# STM32.net
KiCad netlist of a schematic drawn in Altium Designer
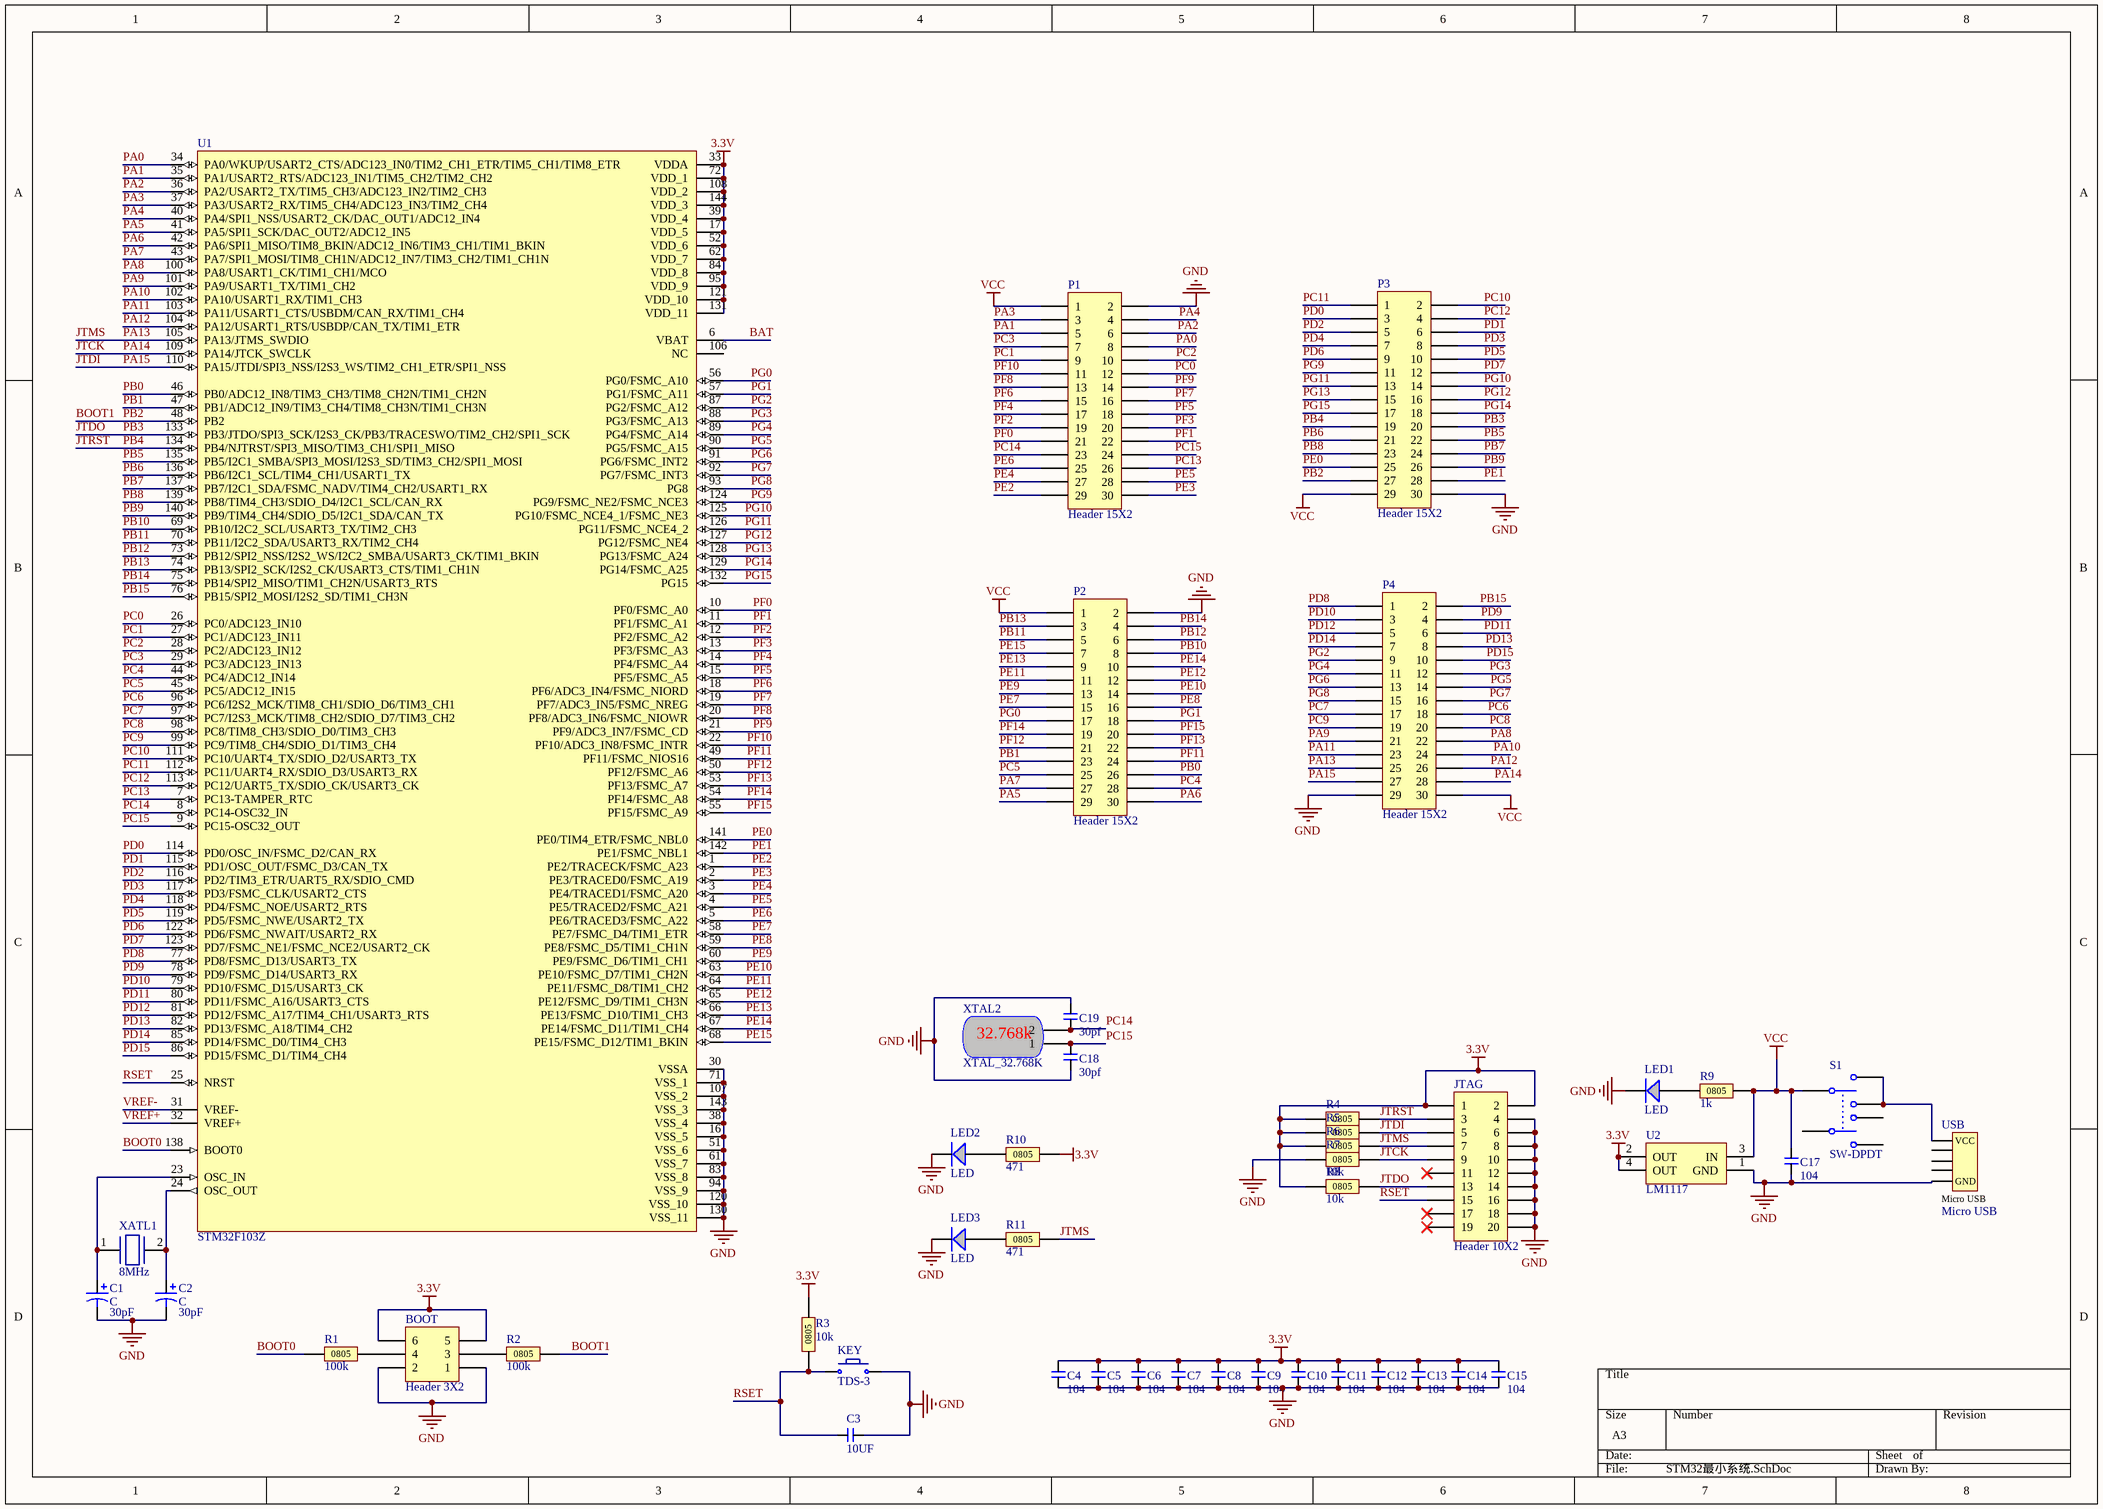
[diagram p0: STM32最小系统.SchDoc]

(export (version "E")
  (design (tool "Eeschema 10.0.6"))
  (components
    (comp (ref "BOOT")
      (value "Header 3X2")
      (footprint "HDR2X3")
      (description "Header, 3-Pin, Dual row")
      (fields (field (name "PUBLISHER") "Altium Limited"))
      (libsource (lib "Miscellaneous Connectors") (part "Header 3X2"))
    )
    (comp (ref "C1")
      (value "C")
      (footprint "C0805")
      (description "Polarized Capacitor (Surface Mount)")
      (fields (field (name "ALTIUM_VALUE") "30pF") (field (name "PUBLISHER") "Altium Limited"))
      (libsource (lib "Miscellaneous Devices") (part "Cap Pol3"))
    )
    (comp (ref "C2")
      (value "C")
      (footprint "C0805")
      (description "Polarized Capacitor (Surface Mount)")
      (fields (field (name "ALTIUM_VALUE") "30pF") (field (name "PUBLISHER") "Altium Limited"))
      (libsource (lib "Miscellaneous Devices") (part "Cap Pol3"))
    )
    (comp (ref "C3") (value "10UF") (footprint "C0805") (libsource (lib "My_Chip") (part "Cap_0805")))
    (comp (ref "C4") (value "104") (footprint "C0805") (libsource (lib "My_Chip") (part "Cap_0805")))
    (comp (ref "C5") (value "104") (footprint "C0805") (libsource (lib "My_Chip") (part "Cap_0805")))
    (comp (ref "C6") (value "104") (footprint "C0805") (libsource (lib "My_Chip") (part "Cap_0805")))
    (comp (ref "C7") (value "104") (footprint "C0805") (libsource (lib "My_Chip") (part "Cap_0805")))
    (comp (ref "C8") (value "104") (footprint "C0805") (libsource (lib "My_Chip") (part "Cap_0805")))
    (comp (ref "C9") (value "104") (footprint "C0805") (libsource (lib "My_Chip") (part "Cap_0805")))
    (comp (ref "C10") (value "104") (footprint "C0805") (libsource (lib "My_Chip") (part "Cap_0805")))
    (comp (ref "C11") (value "104") (footprint "C0805") (libsource (lib "My_Chip") (part "Cap_0805")))
    (comp (ref "C12") (value "104") (footprint "C0805") (libsource (lib "My_Chip") (part "Cap_0805")))
    (comp (ref "C13") (value "104") (footprint "C0805") (libsource (lib "My_Chip") (part "Cap_0805")))
    (comp (ref "C14") (value "104") (footprint "C0805") (libsource (lib "My_Chip") (part "Cap_0805")))
    (comp (ref "C15") (value "104") (footprint "C0805") (libsource (lib "My_Chip") (part "Cap_0805")))
    (comp (ref "C17") (value "104") (footprint "C0805") (libsource (lib "My_Chip") (part "Cap_0805")))
    (comp (ref "C18") (value "30pf") (footprint "C0805") (libsource (lib "My_Chip") (part "Cap_0805")))
    (comp (ref "C19") (value "30pf") (footprint "C0805") (libsource (lib "My_Chip") (part "Cap_0805")))
    (comp (ref "JTAG")
      (value "Header 10X2")
      (footprint "JTAG - duplicate1")
      (description "Header, 10-Pin, Dual row")
      (fields (field (name "PUBLISHER") "Altium Limited"))
      (libsource (lib "Miscellaneous Connectors") (part "Header 10X2"))
    )
    (comp (ref "KEY") (value "TDS-3") (footprint "TDS-3") (libsource (lib "My_Chip") (part "TDS-3")))
    (comp (ref "LED1") (value "LED") (footprint "LED") (libsource (lib "My_Chip") (part "LED")))
    (comp (ref "LED2") (value "LED") (footprint "LED") (libsource (lib "My_Chip") (part "LED")))
    (comp (ref "LED3") (value "LED") (footprint "LED") (libsource (lib "My_Chip") (part "LED")))
    (comp (ref "P1")
      (value "Header 15X2")
      (footprint "HDR2X15")
      (description "Header, 15-Pin, Dual row")
      (fields (field (name "PUBLISHER") "Altium Limited"))
      (libsource (lib "Miscellaneous Connectors") (part "Header 15X2"))
    )
    (comp (ref "P2")
      (value "Header 15X2")
      (footprint "HDR2X15")
      (description "Header, 15-Pin, Dual row")
      (fields (field (name "PUBLISHER") "Altium Limited"))
      (libsource (lib "Miscellaneous Connectors") (part "Header 15X2"))
    )
    (comp (ref "P3")
      (value "Header 15X2")
      (footprint "HDR2X15")
      (description "Header, 15-Pin, Dual row")
      (fields (field (name "PUBLISHER") "Altium Limited"))
      (libsource (lib "Miscellaneous Connectors") (part "Header 15X2"))
    )
    (comp (ref "P4")
      (value "Header 15X2")
      (footprint "HDR2X15")
      (description "Header, 15-Pin, Dual row")
      (fields (field (name "PUBLISHER") "Altium Limited"))
      (libsource (lib "Miscellaneous Connectors") (part "Header 15X2"))
    )
    (comp (ref "R1")
      (value "100k")
      (footprint "PCBComponent_1 - duplicate1")
      (libsource (lib "PCB集成库") (part "贴片电阻"))
    )
    (comp (ref "R2")
      (value "100k")
      (footprint "PCBComponent_1 - duplicate1")
      (libsource (lib "PCB集成库") (part "贴片电阻"))
    )
    (comp (ref "R3")
      (value "10k")
      (footprint "PCBComponent_1 - duplicate1")
      (libsource (lib "") (part "贴片电阻_1"))
    )
    (comp (ref "R4")
      (value "10k")
      (footprint "PCBComponent_1 - duplicate1")
      (libsource (lib "PCB集成库") (part "贴片电阻"))
    )
    (comp (ref "R5")
      (value "10k")
      (footprint "PCBComponent_1 - duplicate1")
      (libsource (lib "PCB集成库") (part "贴片电阻"))
    )
    (comp (ref "R6")
      (value "10k")
      (footprint "PCBComponent_1 - duplicate1")
      (libsource (lib "PCB集成库") (part "贴片电阻"))
    )
    (comp (ref "R7")
      (value "10k")
      (footprint "PCBComponent_1 - duplicate1")
      (libsource (lib "PCB集成库") (part "贴片电阻"))
    )
    (comp (ref "R8")
      (value "10k")
      (footprint "PCBComponent_1 - duplicate1")
      (libsource (lib "PCB集成库") (part "贴片电阻"))
    )
    (comp (ref "R9")
      (value "1k")
      (footprint "PCBComponent_1 - duplicate1")
      (libsource (lib "PCB集成库") (part "贴片电阻"))
    )
    (comp (ref "R10")
      (value "471")
      (footprint "PCBComponent_1 - duplicate1")
      (libsource (lib "PCB集成库") (part "贴片电阻"))
    )
    (comp (ref "R11")
      (value "471")
      (footprint "PCBComponent_1 - duplicate1")
      (libsource (lib "PCB集成库") (part "贴片电阻"))
    )
    (comp (ref "S1")
      (value "SW-DPDT")
      (footprint "DPDT-6")
      (description "Double-Pole, Double-Throw Switch")
      (fields (field (name "PUBLISHER") "Altium Limited"))
      (libsource (lib "Miscellaneous Devices") (part "SW-DPDT"))
    )
    (comp (ref "U1")
      (value "STM32F103Z")
      (footprint "LQFP-144N")
      (libsource (lib "stm32") (part "STM32F103Z_T"))
    )
    (comp (ref "U2") (value "LM1117") (footprint "SOT-223") (libsource (lib "My_Chip") (part "LM1117")))
    (comp (ref "USB")
      (value "Micro USB")
      (footprint "PCBComponent_1 - duplicate2")
      (libsource (lib "PCB集成库") (part "Micro USB"))
    )
    (comp (ref "XATL1") (value "8MHz") (footprint "49/S_N") (libsource (lib "My_Chip") (part "XATL")))
    (comp (ref "XTAL2")
      (value "XTAL_32.768K")
      (footprint "XTAL_32.768K")
      (libsource (lib "My_Chip") (part "XTAL_32.768K"))
    )
  )
  (nets
    (net (code "1") (name "/BAT") (class "Default")
      (node (ref "U1") (pin "6") (pinfunction "VBAT_6") (pintype "power_in"))
    )
    (net (code "2") (name "/BOOT0") (class "Default")
      (node (ref "R1") (pin "1") (pinfunction "10_1") (pintype "passive"))
      (node (ref "U1") (pin "138") (pinfunction "BOOT0_138") (pintype "input"))
    )
    (net (code "3") (name "/BOOT1") (class "Default")
      (node (ref "P3") (pin "27") (pinfunction "27_27") (pintype "passive"))
      (node (ref "R2") (pin "2") (pinfunction "11_2") (pintype "passive"))
      (node (ref "U1") (pin "48") (pinfunction "PB2_48") (pintype "bidirectional"))
    )
    (net (code "4") (name "/JTCK") (class "Default")
      (node (ref "JTAG") (pin "9") (pinfunction "9_9") (pintype "passive"))
      (node (ref "P4") (pin "28") (pinfunction "28_28") (pintype "passive"))
      (node (ref "R7") (pin "2") (pinfunction "11_2") (pintype "passive"))
      (node (ref "U1") (pin "109") (pinfunction "PA14/JTCK_SWCLK_109") (pintype "bidirectional"))
    )
    (net (code "5") (name "/JTDI") (class "Default")
      (node (ref "JTAG") (pin "5") (pinfunction "5_5") (pintype "passive"))
      (node (ref "P4") (pin "27") (pinfunction "27_27") (pintype "passive"))
      (node (ref "R5") (pin "2") (pinfunction "11_2") (pintype "passive"))
      (node (ref "U1") (pin "110") (pinfunction "PA15/JTDI/SPI3_NSS/I2S3_WS/TIM2_CH1_ETR/SPI1_NSS_110") (pintype "bidirectional"))
    )
    (net (code "6") (name "/JTDO") (class "Default")
      (node (ref "JTAG") (pin "13") (pinfunction "13_13") (pintype "passive"))
      (node (ref "P3") (pin "20") (pinfunction "20_20") (pintype "passive"))
      (node (ref "R8") (pin "2") (pinfunction "11_2") (pintype "passive"))
      (node (ref "U1") (pin "133") (pinfunction "PB3/JTDO/SPI3_SCK/I2S3_CK/PB3/TRACESWO/TIM2_CH2/SPI1_SCK_133") (pintype "bidirectional"))
    )
    (net (code "7") (name "/JTMS") (class "Default")
      (node (ref "JTAG") (pin "7") (pinfunction "7_7") (pintype "passive"))
      (node (ref "P4") (pin "25") (pinfunction "25_25") (pintype "passive"))
      (node (ref "R11") (pin "2") (pinfunction "11_2") (pintype "passive"))
      (node (ref "R6") (pin "2") (pinfunction "11_2") (pintype "passive"))
      (node (ref "U1") (pin "105") (pinfunction "PA13/JTMS_SWDIO_105") (pintype "bidirectional"))
    )
    (net (code "8") (name "/JTRST") (class "Default")
      (node (ref "JTAG") (pin "3") (pinfunction "3_3") (pintype "passive"))
      (node (ref "P3") (pin "19") (pinfunction "19_19") (pintype "passive"))
      (node (ref "R4") (pin "2") (pinfunction "11_2") (pintype "passive"))
      (node (ref "U1") (pin "134") (pinfunction "PB4/NJTRST/SPI3_MISO/TIM3_CH1/SPI1_MISO_134") (pintype "bidirectional"))
    )
    (net (code "9") (name "/PA0") (class "Default")
      (node (ref "P1") (pin "8") (pinfunction "8_8") (pintype "passive"))
      (node (ref "U1") (pin "34") (pinfunction "PA0/WKUP/USART2_CTS/ADC123_IN0/TIM2_CH1_ETR/TIM5_CH1/TIM8_ETR_34") (pintype "bidirectional"))
    )
    (net (code "10") (name "/PA1") (class "Default")
      (node (ref "P1") (pin "5") (pinfunction "5_5") (pintype "passive"))
      (node (ref "U1") (pin "35") (pinfunction "PA1/USART2_RTS/ADC123_IN1/TIM5_CH2/TIM2_CH2_35") (pintype "bidirectional"))
    )
    (net (code "11") (name "/PA2") (class "Default")
      (node (ref "P1") (pin "6") (pinfunction "6_6") (pintype "passive"))
      (node (ref "U1") (pin "36") (pinfunction "PA2/USART2_TX/TIM5_CH3/ADC123_IN2/TIM2_CH3_36") (pintype "bidirectional"))
    )
    (net (code "12") (name "/PA3") (class "Default")
      (node (ref "P1") (pin "3") (pinfunction "3_3") (pintype "passive"))
      (node (ref "U1") (pin "37") (pinfunction "PA3/USART2_RX/TIM5_CH4/ADC123_IN3/TIM2_CH4_37") (pintype "bidirectional"))
    )
    (net (code "13") (name "/PA4") (class "Default")
      (node (ref "P1") (pin "4") (pinfunction "4_4") (pintype "passive"))
      (node (ref "U1") (pin "40") (pinfunction "PA4/SPI1_NSS/USART2_CK/DAC_OUT1/ADC12_IN4_40") (pintype "bidirectional"))
    )
    (net (code "14") (name "/PA5") (class "Default")
      (node (ref "P2") (pin "29") (pinfunction "29_29") (pintype "passive"))
      (node (ref "U1") (pin "41") (pinfunction "PA5/SPI1_SCK/DAC_OUT2/ADC12_IN5_41") (pintype "bidirectional"))
    )
    (net (code "15") (name "/PA6") (class "Default")
      (node (ref "P2") (pin "30") (pinfunction "30_30") (pintype "passive"))
      (node (ref "U1") (pin "42") (pinfunction "PA6/SPI1_MISO/TIM8_BKIN/ADC12_IN6/TIM3_CH1/TIM1_BKIN_42") (pintype "bidirectional"))
    )
    (net (code "16") (name "/PA7") (class "Default")
      (node (ref "P2") (pin "27") (pinfunction "27_27") (pintype "passive"))
      (node (ref "U1") (pin "43") (pinfunction "PA7/SPI1_MOSI/TIM8_CH1N/ADC12_IN7/TIM3_CH2/TIM1_CH1N_43") (pintype "bidirectional"))
    )
    (net (code "17") (name "/PA8") (class "Default")
      (node (ref "P4") (pin "22") (pinfunction "22_22") (pintype "passive"))
      (node (ref "U1") (pin "100") (pinfunction "PA8/USART1_CK/TIM1_CH1/MCO_100") (pintype "bidirectional"))
    )
    (net (code "18") (name "/PA9") (class "Default")
      (node (ref "P4") (pin "21") (pinfunction "21_21") (pintype "passive"))
      (node (ref "U1") (pin "101") (pinfunction "PA9/USART1_TX/TIM1_CH2_101") (pintype "bidirectional"))
    )
    (net (code "19") (name "/PA10") (class "Default")
      (node (ref "P4") (pin "24") (pinfunction "24_24") (pintype "passive"))
      (node (ref "U1") (pin "102") (pinfunction "PA10/USART1_RX/TIM1_CH3_102") (pintype "bidirectional"))
    )
    (net (code "20") (name "/PA11") (class "Default")
      (node (ref "P4") (pin "23") (pinfunction "23_23") (pintype "passive"))
      (node (ref "U1") (pin "103") (pinfunction "PA11/USART1_CTS/USBDM/CAN_RX/TIM1_CH4_103") (pintype "bidirectional"))
    )
    (net (code "21") (name "/PA12") (class "Default")
      (node (ref "P4") (pin "26") (pinfunction "26_26") (pintype "passive"))
      (node (ref "U1") (pin "104") (pinfunction "PA12/USART1_RTS/USBDP/CAN_TX/TIM1_ETR_104") (pintype "bidirectional"))
    )
    (net (code "22") (name "/PB0") (class "Default")
      (node (ref "P2") (pin "26") (pinfunction "26_26") (pintype "passive"))
      (node (ref "U1") (pin "46") (pinfunction "PB0/ADC12_IN8/TIM3_CH3/TIM8_CH2N/TIM1_CH2N_46") (pintype "bidirectional"))
    )
    (net (code "23") (name "/PB1") (class "Default")
      (node (ref "P2") (pin "23") (pinfunction "23_23") (pintype "passive"))
      (node (ref "U1") (pin "47") (pinfunction "PB1/ADC12_IN9/TIM3_CH4/TIM8_CH3N/TIM1_CH3N_47") (pintype "bidirectional"))
    )
    (net (code "24") (name "/PB5") (class "Default")
      (node (ref "P3") (pin "22") (pinfunction "22_22") (pintype "passive"))
      (node (ref "U1") (pin "135") (pinfunction "PB5/I2C1_SMBA/SPI3_MOSI/I2S3_SD/TIM3_CH2/SPI1_MOSI_135") (pintype "bidirectional"))
    )
    (net (code "25") (name "/PB6") (class "Default")
      (node (ref "P3") (pin "21") (pinfunction "21_21") (pintype "passive"))
      (node (ref "U1") (pin "136") (pinfunction "PB6/I2C1_SCL/TIM4_CH1/USART1_TX_136") (pintype "bidirectional"))
    )
    (net (code "26") (name "/PB7") (class "Default")
      (node (ref "P3") (pin "24") (pinfunction "24_24") (pintype "passive"))
      (node (ref "U1") (pin "137") (pinfunction "PB7/I2C1_SDA/FSMC_NADV/TIM4_CH2/USART1_RX_137") (pintype "bidirectional"))
    )
    (net (code "27") (name "/PB8") (class "Default")
      (node (ref "P3") (pin "23") (pinfunction "23_23") (pintype "passive"))
      (node (ref "U1") (pin "139") (pinfunction "PB8/TIM4_CH3/SDIO_D4/I2C1_SCL/CAN_RX_139") (pintype "bidirectional"))
    )
    (net (code "28") (name "/PB9") (class "Default")
      (node (ref "P3") (pin "26") (pinfunction "26_26") (pintype "passive"))
      (node (ref "U1") (pin "140") (pinfunction "PB9/TIM4_CH4/SDIO_D5/I2C1_SDA/CAN_TX_140") (pintype "bidirectional"))
    )
    (net (code "29") (name "/PB10") (class "Default")
      (node (ref "P2") (pin "8") (pinfunction "8_8") (pintype "passive"))
      (node (ref "U1") (pin "69") (pinfunction "PB10/I2C2_SCL/USART3_TX/TIM2_CH3_69") (pintype "bidirectional"))
    )
    (net (code "30") (name "/PB11") (class "Default")
      (node (ref "P2") (pin "5") (pinfunction "5_5") (pintype "passive"))
      (node (ref "U1") (pin "70") (pinfunction "PB11/I2C2_SDA/USART3_RX/TIM2_CH4_70") (pintype "bidirectional"))
    )
    (net (code "31") (name "/PB12") (class "Default")
      (node (ref "P2") (pin "6") (pinfunction "6_6") (pintype "passive"))
      (node (ref "U1") (pin "73") (pinfunction "PB12/SPI2_NSS/I2S2_WS/I2C2_SMBA/USART3_CK/TIM1_BKIN_73") (pintype "bidirectional"))
    )
    (net (code "32") (name "/PB13") (class "Default")
      (node (ref "P2") (pin "3") (pinfunction "3_3") (pintype "passive"))
      (node (ref "U1") (pin "74") (pinfunction "PB13/SPI2_SCK/I2S2_CK/USART3_CTS/TIM1_CH1N_74") (pintype "bidirectional"))
    )
    (net (code "33") (name "/PB14") (class "Default")
      (node (ref "P2") (pin "4") (pinfunction "4_4") (pintype "passive"))
      (node (ref "U1") (pin "75") (pinfunction "PB14/SPI2_MISO/TIM1_CH2N/USART3_RTS_75") (pintype "bidirectional"))
    )
    (net (code "34") (name "/PB15") (class "Default")
      (node (ref "P4") (pin "2") (pinfunction "2_2") (pintype "passive"))
      (node (ref "U1") (pin "76") (pinfunction "PB15/SPI2_MOSI/I2S2_SD/TIM1_CH3N_76") (pintype "bidirectional"))
    )
    (net (code "35") (name "/PC0") (class "Default")
      (node (ref "P1") (pin "12") (pinfunction "12_12") (pintype "passive"))
      (node (ref "U1") (pin "26") (pinfunction "PC0/ADC123_IN10_26") (pintype "bidirectional"))
    )
    (net (code "36") (name "/PC1") (class "Default")
      (node (ref "P1") (pin "9") (pinfunction "9_9") (pintype "passive"))
      (node (ref "U1") (pin "27") (pinfunction "PC1/ADC123_IN11_27") (pintype "bidirectional"))
    )
    (net (code "37") (name "/PC2") (class "Default")
      (node (ref "P1") (pin "10") (pinfunction "10_10") (pintype "passive"))
      (node (ref "U1") (pin "28") (pinfunction "PC2/ADC123_IN12_28") (pintype "bidirectional"))
    )
    (net (code "38") (name "/PC3") (class "Default")
      (node (ref "P1") (pin "7") (pinfunction "7_7") (pintype "passive"))
      (node (ref "U1") (pin "29") (pinfunction "PC3/ADC123_IN13_29") (pintype "bidirectional"))
    )
    (net (code "39") (name "/PC4") (class "Default")
      (node (ref "P2") (pin "28") (pinfunction "28_28") (pintype "passive"))
      (node (ref "U1") (pin "44") (pinfunction "PC4/ADC12_IN14_44") (pintype "bidirectional"))
    )
    (net (code "40") (name "/PC5") (class "Default")
      (node (ref "P2") (pin "25") (pinfunction "25_25") (pintype "passive"))
      (node (ref "U1") (pin "45") (pinfunction "PC5/ADC12_IN15_45") (pintype "bidirectional"))
    )
    (net (code "41") (name "/PC6") (class "Default")
      (node (ref "P4") (pin "18") (pinfunction "18_18") (pintype "passive"))
      (node (ref "U1") (pin "96") (pinfunction "PC6/I2S2_MCK/TIM8_CH1/SDIO_D6/TIM3_CH1_96") (pintype "bidirectional"))
    )
    (net (code "42") (name "/PC7") (class "Default")
      (node (ref "P4") (pin "17") (pinfunction "17_17") (pintype "passive"))
      (node (ref "U1") (pin "97") (pinfunction "PC7/I2S3_MCK/TIM8_CH2/SDIO_D7/TIM3_CH2_97") (pintype "bidirectional"))
    )
    (net (code "43") (name "/PC8") (class "Default")
      (node (ref "P4") (pin "20") (pinfunction "20_20") (pintype "passive"))
      (node (ref "U1") (pin "98") (pinfunction "PC8/TIM8_CH3/SDIO_D0/TIM3_CH3_98") (pintype "bidirectional"))
    )
    (net (code "44") (name "/PC9") (class "Default")
      (node (ref "P4") (pin "19") (pinfunction "19_19") (pintype "passive"))
      (node (ref "U1") (pin "99") (pinfunction "PC9/TIM8_CH4/SDIO_D1/TIM3_CH4_99") (pintype "bidirectional"))
    )
    (net (code "45") (name "/PC10") (class "Default")
      (node (ref "P3") (pin "2") (pinfunction "2_2") (pintype "passive"))
      (node (ref "U1") (pin "111") (pinfunction "PC10/UART4_TX/SDIO_D2/USART3_TX_111") (pintype "bidirectional"))
    )
    (net (code "46") (name "/PC11") (class "Default")
      (node (ref "P3") (pin "1") (pinfunction "1_1") (pintype "passive"))
      (node (ref "U1") (pin "112") (pinfunction "PC11/UART4_RX/SDIO_D3/USART3_RX_112") (pintype "bidirectional"))
    )
    (net (code "47") (name "/PC12") (class "Default")
      (node (ref "P3") (pin "4") (pinfunction "4_4") (pintype "passive"))
      (node (ref "U1") (pin "113") (pinfunction "PC12/UART5_TX/SDIO_CK/USART3_CK_113") (pintype "bidirectional"))
    )
    (net (code "48") (name "/PC13") (class "Default")
      (node (ref "P1") (pin "26") (pinfunction "26_26") (pintype "passive"))
      (node (ref "U1") (pin "7") (pinfunction "PC13-TAMPER_RTC_7") (pintype "bidirectional"))
    )
    (net (code "49") (name "/PC14") (class "Default")
      (node (ref "C19") (pin "1") (pinfunction "1_1") (pintype "passive"))
      (node (ref "P1") (pin "23") (pinfunction "23_23") (pintype "passive"))
      (node (ref "U1") (pin "8") (pinfunction "PC14-OSC32_IN_8") (pintype "bidirectional"))
      (node (ref "XTAL2") (pin "2") (pinfunction "2_2") (pintype "passive"))
    )
    (net (code "50") (name "/PC15") (class "Default")
      (node (ref "C18") (pin "2") (pinfunction "2_2") (pintype "passive"))
      (node (ref "P1") (pin "24") (pinfunction "24_24") (pintype "passive"))
      (node (ref "U1") (pin "9") (pinfunction "PC15-OSC32_OUT_9") (pintype "bidirectional"))
      (node (ref "XTAL2") (pin "1") (pinfunction "1_1") (pintype "passive"))
    )
    (net (code "51") (name "/PD0") (class "Default")
      (node (ref "P3") (pin "3") (pinfunction "3_3") (pintype "passive"))
      (node (ref "U1") (pin "114") (pinfunction "PD0/OSC_IN/FSMC_D2/CAN_RX_114") (pintype "bidirectional"))
    )
    (net (code "52") (name "/PD1") (class "Default")
      (node (ref "P3") (pin "6") (pinfunction "6_6") (pintype "passive"))
      (node (ref "U1") (pin "115") (pinfunction "PD1/OSC_OUT/FSMC_D3/CAN_TX_115") (pintype "bidirectional"))
    )
    (net (code "53") (name "/PD2") (class "Default")
      (node (ref "P3") (pin "5") (pinfunction "5_5") (pintype "passive"))
      (node (ref "U1") (pin "116") (pinfunction "PD2/TIM3_ETR/UART5_RX/SDIO_CMD_116") (pintype "bidirectional"))
    )
    (net (code "54") (name "/PD3") (class "Default")
      (node (ref "P3") (pin "8") (pinfunction "8_8") (pintype "passive"))
      (node (ref "U1") (pin "117") (pinfunction "PD3/FSMC_CLK/USART2_CTS_117") (pintype "bidirectional"))
    )
    (net (code "55") (name "/PD4") (class "Default")
      (node (ref "P3") (pin "7") (pinfunction "7_7") (pintype "passive"))
      (node (ref "U1") (pin "118") (pinfunction "PD4/FSMC_NOE/USART2_RTS_118") (pintype "bidirectional"))
    )
    (net (code "56") (name "/PD5") (class "Default")
      (node (ref "P3") (pin "10") (pinfunction "10_10") (pintype "passive"))
      (node (ref "U1") (pin "119") (pinfunction "PD5/FSMC_NWE/USART2_TX_119") (pintype "bidirectional"))
    )
    (net (code "57") (name "/PD6") (class "Default")
      (node (ref "P3") (pin "9") (pinfunction "9_9") (pintype "passive"))
      (node (ref "U1") (pin "122") (pinfunction "PD6/FSMC_NWAIT/USART2_RX_122") (pintype "bidirectional"))
    )
    (net (code "58") (name "/PD7") (class "Default")
      (node (ref "P3") (pin "12") (pinfunction "12_12") (pintype "passive"))
      (node (ref "U1") (pin "123") (pinfunction "PD7/FSMC_NE1/FSMC_NCE2/USART2_CK_123") (pintype "bidirectional"))
    )
    (net (code "59") (name "/PD8") (class "Default")
      (node (ref "P4") (pin "1") (pinfunction "1_1") (pintype "passive"))
      (node (ref "U1") (pin "77") (pinfunction "PD8/FSMC_D13/USART3_TX_77") (pintype "bidirectional"))
    )
    (net (code "60") (name "/PD9") (class "Default")
      (node (ref "P4") (pin "4") (pinfunction "4_4") (pintype "passive"))
      (node (ref "U1") (pin "78") (pinfunction "PD9/FSMC_D14/USART3_RX_78") (pintype "bidirectional"))
    )
    (net (code "61") (name "/PD10") (class "Default")
      (node (ref "P4") (pin "3") (pinfunction "3_3") (pintype "passive"))
      (node (ref "U1") (pin "79") (pinfunction "PD10/FSMC_D15/USART3_CK_79") (pintype "bidirectional"))
    )
    (net (code "62") (name "/PD11") (class "Default")
      (node (ref "P4") (pin "6") (pinfunction "6_6") (pintype "passive"))
      (node (ref "U1") (pin "80") (pinfunction "PD11/FSMC_A16/USART3_CTS_80") (pintype "bidirectional"))
    )
    (net (code "63") (name "/PD12") (class "Default")
      (node (ref "P4") (pin "5") (pinfunction "5_5") (pintype "passive"))
      (node (ref "U1") (pin "81") (pinfunction "PD12/FSMC_A17/TIM4_CH1/USART3_RTS_81") (pintype "bidirectional"))
    )
    (net (code "64") (name "/PD13") (class "Default")
      (node (ref "P4") (pin "8") (pinfunction "8_8") (pintype "passive"))
      (node (ref "U1") (pin "82") (pinfunction "PD13/FSMC_A18/TIM4_CH2_82") (pintype "bidirectional"))
    )
    (net (code "65") (name "/PD14") (class "Default")
      (node (ref "P4") (pin "7") (pinfunction "7_7") (pintype "passive"))
      (node (ref "U1") (pin "85") (pinfunction "PD14/FSMC_D0/TIM4_CH3_85") (pintype "bidirectional"))
    )
    (net (code "66") (name "/PD15") (class "Default")
      (node (ref "P4") (pin "10") (pinfunction "10_10") (pintype "passive"))
      (node (ref "U1") (pin "86") (pinfunction "PD15/FSMC_D1/TIM4_CH4_86") (pintype "bidirectional"))
    )
    (net (code "67") (name "/PE0") (class "Default")
      (node (ref "P3") (pin "25") (pinfunction "25_25") (pintype "passive"))
      (node (ref "U1") (pin "141") (pinfunction "PE0/TIM4_ETR/FSMC_NBL0_141") (pintype "bidirectional"))
    )
    (net (code "68") (name "/PE1") (class "Default")
      (node (ref "P3") (pin "28") (pinfunction "28_28") (pintype "passive"))
      (node (ref "U1") (pin "142") (pinfunction "PE1/FSMC_NBL1_142") (pintype "bidirectional"))
    )
    (net (code "69") (name "/PE2") (class "Default")
      (node (ref "P1") (pin "29") (pinfunction "29_29") (pintype "passive"))
      (node (ref "U1") (pin "1") (pinfunction "PE2/TRACECK/FSMC_A23_1") (pintype "bidirectional"))
    )
    (net (code "70") (name "/PE3") (class "Default")
      (node (ref "P1") (pin "30") (pinfunction "30_30") (pintype "passive"))
      (node (ref "U1") (pin "2") (pinfunction "PE3/TRACED0/FSMC_A19_2") (pintype "bidirectional"))
    )
    (net (code "71") (name "/PE4") (class "Default")
      (node (ref "P1") (pin "27") (pinfunction "27_27") (pintype "passive"))
      (node (ref "U1") (pin "3") (pinfunction "PE4/TRACED1/FSMC_A20_3") (pintype "bidirectional"))
    )
    (net (code "72") (name "/PE5") (class "Default")
      (node (ref "P1") (pin "28") (pinfunction "28_28") (pintype "passive"))
      (node (ref "U1") (pin "4") (pinfunction "PE5/TRACED2/FSMC_A21_4") (pintype "bidirectional"))
    )
    (net (code "73") (name "/PE6") (class "Default")
      (node (ref "P1") (pin "25") (pinfunction "25_25") (pintype "passive"))
      (node (ref "U1") (pin "5") (pinfunction "PE6/TRACED3/FSMC_A22_5") (pintype "bidirectional"))
    )
    (net (code "74") (name "/PE7") (class "Default")
      (node (ref "P2") (pin "15") (pinfunction "15_15") (pintype "passive"))
      (node (ref "U1") (pin "58") (pinfunction "PE7/FSMC_D4/TIM1_ETR_58") (pintype "bidirectional"))
    )
    (net (code "75") (name "/PE8") (class "Default")
      (node (ref "P2") (pin "16") (pinfunction "16_16") (pintype "passive"))
      (node (ref "U1") (pin "59") (pinfunction "PE8/FSMC_D5/TIM1_CH1N_59") (pintype "bidirectional"))
    )
    (net (code "76") (name "/PE9") (class "Default")
      (node (ref "P2") (pin "13") (pinfunction "13_13") (pintype "passive"))
      (node (ref "U1") (pin "60") (pinfunction "PE9/FSMC_D6/TIM1_CH1_60") (pintype "bidirectional"))
    )
    (net (code "77") (name "/PE10") (class "Default")
      (node (ref "P2") (pin "14") (pinfunction "14_14") (pintype "passive"))
      (node (ref "U1") (pin "63") (pinfunction "PE10/FSMC_D7/TIM1_CH2N_63") (pintype "bidirectional"))
    )
    (net (code "78") (name "/PE11") (class "Default")
      (node (ref "P2") (pin "11") (pinfunction "11_11") (pintype "passive"))
      (node (ref "U1") (pin "64") (pinfunction "PE11/FSMC_D8/TIM1_CH2_64") (pintype "bidirectional"))
    )
    (net (code "79") (name "/PE12") (class "Default")
      (node (ref "P2") (pin "12") (pinfunction "12_12") (pintype "passive"))
      (node (ref "U1") (pin "65") (pinfunction "PE12/FSMC_D9/TIM1_CH3N_65") (pintype "bidirectional"))
    )
    (net (code "80") (name "/PE13") (class "Default")
      (node (ref "P2") (pin "9") (pinfunction "9_9") (pintype "passive"))
      (node (ref "U1") (pin "66") (pinfunction "PE13/FSMC_D10/TIM1_CH3_66") (pintype "bidirectional"))
    )
    (net (code "81") (name "/PE14") (class "Default")
      (node (ref "P2") (pin "10") (pinfunction "10_10") (pintype "passive"))
      (node (ref "U1") (pin "67") (pinfunction "PE14/FSMC_D11/TIM1_CH4_67") (pintype "bidirectional"))
    )
    (net (code "82") (name "/PE15") (class "Default")
      (node (ref "P2") (pin "7") (pinfunction "7_7") (pintype "passive"))
      (node (ref "U1") (pin "68") (pinfunction "PE15/FSMC_D12/TIM1_BKIN_68") (pintype "bidirectional"))
    )
    (net (code "83") (name "/PF0") (class "Default")
      (node (ref "P1") (pin "21") (pinfunction "21_21") (pintype "passive"))
      (node (ref "U1") (pin "10") (pinfunction "PF0/FSMC_A0_10") (pintype "bidirectional"))
    )
    (net (code "84") (name "/PF1") (class "Default")
      (node (ref "P1") (pin "22") (pinfunction "22_22") (pintype "passive"))
      (node (ref "U1") (pin "11") (pinfunction "PF1/FSMC_A1_11") (pintype "bidirectional"))
    )
    (net (code "85") (name "/PF2") (class "Default")
      (node (ref "P1") (pin "19") (pinfunction "19_19") (pintype "passive"))
      (node (ref "U1") (pin "12") (pinfunction "PF2/FSMC_A2_12") (pintype "bidirectional"))
    )
    (net (code "86") (name "/PF3") (class "Default")
      (node (ref "P1") (pin "20") (pinfunction "20_20") (pintype "passive"))
      (node (ref "U1") (pin "13") (pinfunction "PF3/FSMC_A3_13") (pintype "bidirectional"))
    )
    (net (code "87") (name "/PF4") (class "Default")
      (node (ref "P1") (pin "17") (pinfunction "17_17") (pintype "passive"))
      (node (ref "U1") (pin "14") (pinfunction "PF4/FSMC_A4_14") (pintype "bidirectional"))
    )
    (net (code "88") (name "/PF5") (class "Default")
      (node (ref "P1") (pin "18") (pinfunction "18_18") (pintype "passive"))
      (node (ref "U1") (pin "15") (pinfunction "PF5/FSMC_A5_15") (pintype "bidirectional"))
    )
    (net (code "89") (name "/PF6") (class "Default")
      (node (ref "P1") (pin "15") (pinfunction "15_15") (pintype "passive"))
      (node (ref "U1") (pin "18") (pinfunction "PF6/ADC3_IN4/FSMC_NIORD_18") (pintype "bidirectional"))
    )
    (net (code "90") (name "/PF7") (class "Default")
      (node (ref "P1") (pin "16") (pinfunction "16_16") (pintype "passive"))
      (node (ref "U1") (pin "19") (pinfunction "PF7/ADC3_IN5/FSMC_NREG_19") (pintype "bidirectional"))
    )
    (net (code "91") (name "/PF8") (class "Default")
      (node (ref "P1") (pin "13") (pinfunction "13_13") (pintype "passive"))
      (node (ref "U1") (pin "20") (pinfunction "PF8/ADC3_IN6/FSMC_NIOWR_20") (pintype "bidirectional"))
    )
    (net (code "92") (name "/PF9") (class "Default")
      (node (ref "P1") (pin "14") (pinfunction "14_14") (pintype "passive"))
      (node (ref "U1") (pin "21") (pinfunction "PF9/ADC3_IN7/FSMC_CD_21") (pintype "bidirectional"))
    )
    (net (code "93") (name "/PF10") (class "Default")
      (node (ref "P1") (pin "11") (pinfunction "11_11") (pintype "passive"))
      (node (ref "U1") (pin "22") (pinfunction "PF10/ADC3_IN8/FSMC_INTR_22") (pintype "bidirectional"))
    )
    (net (code "94") (name "/PF11") (class "Default")
      (node (ref "P2") (pin "24") (pinfunction "24_24") (pintype "passive"))
      (node (ref "U1") (pin "49") (pinfunction "PF11/FSMC_NIOS16_49") (pintype "bidirectional"))
    )
    (net (code "95") (name "/PF12") (class "Default")
      (node (ref "P2") (pin "21") (pinfunction "21_21") (pintype "passive"))
      (node (ref "U1") (pin "50") (pinfunction "PF12/FSMC_A6_50") (pintype "bidirectional"))
    )
    (net (code "96") (name "/PF13") (class "Default")
      (node (ref "P2") (pin "22") (pinfunction "22_22") (pintype "passive"))
      (node (ref "U1") (pin "53") (pinfunction "PF13/FSMC_A7_53") (pintype "bidirectional"))
    )
    (net (code "97") (name "/PF14") (class "Default")
      (node (ref "P2") (pin "19") (pinfunction "19_19") (pintype "passive"))
      (node (ref "U1") (pin "54") (pinfunction "PF14/FSMC_A8_54") (pintype "bidirectional"))
    )
    (net (code "98") (name "/PF15") (class "Default")
      (node (ref "P2") (pin "20") (pinfunction "20_20") (pintype "passive"))
      (node (ref "U1") (pin "55") (pinfunction "PF15/FSMC_A9_55") (pintype "bidirectional"))
    )
    (net (code "99") (name "/PG0") (class "Default")
      (node (ref "P2") (pin "17") (pinfunction "17_17") (pintype "passive"))
      (node (ref "U1") (pin "56") (pinfunction "PG0/FSMC_A10_56") (pintype "bidirectional"))
    )
    (net (code "100") (name "/PG1") (class "Default")
      (node (ref "P2") (pin "18") (pinfunction "18_18") (pintype "passive"))
      (node (ref "U1") (pin "57") (pinfunction "PG1/FSMC_A11_57") (pintype "bidirectional"))
    )
    (net (code "101") (name "/PG2") (class "Default")
      (node (ref "P4") (pin "9") (pinfunction "9_9") (pintype "passive"))
      (node (ref "U1") (pin "87") (pinfunction "PG2/FSMC_A12_87") (pintype "bidirectional"))
    )
    (net (code "102") (name "/PG3") (class "Default")
      (node (ref "P4") (pin "12") (pinfunction "12_12") (pintype "passive"))
      (node (ref "U1") (pin "88") (pinfunction "PG3/FSMC_A13_88") (pintype "bidirectional"))
    )
    (net (code "103") (name "/PG4") (class "Default")
      (node (ref "P4") (pin "11") (pinfunction "11_11") (pintype "passive"))
      (node (ref "U1") (pin "89") (pinfunction "PG4/FSMC_A14_89") (pintype "bidirectional"))
    )
    (net (code "104") (name "/PG5") (class "Default")
      (node (ref "P4") (pin "14") (pinfunction "14_14") (pintype "passive"))
      (node (ref "U1") (pin "90") (pinfunction "PG5/FSMC_A15_90") (pintype "bidirectional"))
    )
    (net (code "105") (name "/PG6") (class "Default")
      (node (ref "P4") (pin "13") (pinfunction "13_13") (pintype "passive"))
      (node (ref "U1") (pin "91") (pinfunction "PG6/FSMC_INT2_91") (pintype "bidirectional"))
    )
    (net (code "106") (name "/PG7") (class "Default")
      (node (ref "P4") (pin "16") (pinfunction "16_16") (pintype "passive"))
      (node (ref "U1") (pin "92") (pinfunction "PG7/FSMC_INT3_92") (pintype "bidirectional"))
    )
    (net (code "107") (name "/PG8") (class "Default")
      (node (ref "P4") (pin "15") (pinfunction "15_15") (pintype "passive"))
      (node (ref "U1") (pin "93") (pinfunction "PG8_93") (pintype "bidirectional"))
    )
    (net (code "108") (name "/PG9") (class "Default")
      (node (ref "P3") (pin "11") (pinfunction "11_11") (pintype "passive"))
      (node (ref "U1") (pin "124") (pinfunction "PG9/FSMC_NE2/FSMC_NCE3_124") (pintype "bidirectional"))
    )
    (net (code "109") (name "/PG10") (class "Default")
      (node (ref "P3") (pin "14") (pinfunction "14_14") (pintype "passive"))
      (node (ref "U1") (pin "125") (pinfunction "PG10/FSMC_NCE4_1/FSMC_NE3_125") (pintype "bidirectional"))
    )
    (net (code "110") (name "/PG11") (class "Default")
      (node (ref "P3") (pin "13") (pinfunction "13_13") (pintype "passive"))
      (node (ref "U1") (pin "126") (pinfunction "PG11/FSMC_NCE4_2_126") (pintype "bidirectional"))
    )
    (net (code "111") (name "/PG12") (class "Default")
      (node (ref "P3") (pin "16") (pinfunction "16_16") (pintype "passive"))
      (node (ref "U1") (pin "127") (pinfunction "PG12/FSMC_NE4_127") (pintype "bidirectional"))
    )
    (net (code "112") (name "/PG13") (class "Default")
      (node (ref "P3") (pin "15") (pinfunction "15_15") (pintype "passive"))
      (node (ref "U1") (pin "128") (pinfunction "PG13/FSMC_A24_128") (pintype "bidirectional"))
    )
    (net (code "113") (name "/PG14") (class "Default")
      (node (ref "P3") (pin "18") (pinfunction "18_18") (pintype "passive"))
      (node (ref "U1") (pin "129") (pinfunction "PG14/FSMC_A25_129") (pintype "bidirectional"))
    )
    (net (code "114") (name "/PG15") (class "Default")
      (node (ref "P3") (pin "17") (pinfunction "17_17") (pintype "passive"))
      (node (ref "U1") (pin "132") (pinfunction "PG15_132") (pintype "bidirectional"))
    )
    (net (code "115") (name "/RSET") (class "Default")
      (node (ref "C3") (pin "2") (pinfunction "2_2") (pintype "passive"))
      (node (ref "JTAG") (pin "15") (pinfunction "15_15") (pintype "passive"))
      (node (ref "KEY") (pin "1") (pinfunction "1_1") (pintype "passive"))
      (node (ref "R3") (pin "1") (pinfunction "10_1") (pintype "passive"))
      (node (ref "U1") (pin "25") (pinfunction "NRST_25") (pintype "bidirectional"))
    )
    (net (code "116") (name "/VREF+") (class "Default")
      (node (ref "U1") (pin "32") (pinfunction "VREF+_32") (pintype "power_in"))
    )
    (net (code "117") (name "/VREF-") (class "Default")
      (node (ref "U1") (pin "31") (pinfunction "VREF-_31") (pintype "power_in"))
    )
    (net (code "118") (name "3.3V") (class "Default")
      (node (ref "BOOT") (pin "5") (pinfunction "5_5") (pintype "passive"))
      (node (ref "BOOT") (pin "6") (pinfunction "6_6") (pintype "passive"))
      (node (ref "C10") (pin "1") (pinfunction "1_1") (pintype "passive"))
      (node (ref "C11") (pin "1") (pinfunction "1_1") (pintype "passive"))
      (node (ref "C12") (pin "1") (pinfunction "1_1") (pintype "passive"))
      (node (ref "C13") (pin "1") (pinfunction "1_1") (pintype "passive"))
      (node (ref "C14") (pin "1") (pinfunction "1_1") (pintype "passive"))
      (node (ref "C15") (pin "1") (pinfunction "1_1") (pintype "passive"))
      (node (ref "C4") (pin "1") (pinfunction "1_1") (pintype "passive"))
      (node (ref "C5") (pin "1") (pinfunction "1_1") (pintype "passive"))
      (node (ref "C6") (pin "1") (pinfunction "1_1") (pintype "passive"))
      (node (ref "C7") (pin "1") (pinfunction "1_1") (pintype "passive"))
      (node (ref "C8") (pin "1") (pinfunction "1_1") (pintype "passive"))
      (node (ref "C9") (pin "1") (pinfunction "1_1") (pintype "passive"))
      (node (ref "JTAG") (pin "1") (pinfunction "1_1") (pintype "passive"))
      (node (ref "JTAG") (pin "2") (pinfunction "2_2") (pintype "passive"))
      (node (ref "R10") (pin "2") (pinfunction "11_2") (pintype "passive"))
      (node (ref "R3") (pin "2") (pinfunction "11_2") (pintype "passive"))
      (node (ref "R4") (pin "1") (pinfunction "10_1") (pintype "passive"))
      (node (ref "R5") (pin "1") (pinfunction "10_1") (pintype "passive"))
      (node (ref "R6") (pin "1") (pinfunction "10_1") (pintype "passive"))
      (node (ref "R8") (pin "1") (pinfunction "10_1") (pintype "passive"))
      (node (ref "U1") (pin "108") (pinfunction "VDD_2_108") (pintype "power_in"))
      (node (ref "U1") (pin "121") (pinfunction "VDD_10_121") (pintype "power_in"))
      (node (ref "U1") (pin "131") (pinfunction "VDD_11_131") (pintype "power_in"))
      (node (ref "U1") (pin "144") (pinfunction "VDD_3_144") (pintype "power_in"))
      (node (ref "U1") (pin "17") (pinfunction "VDD_5_17") (pintype "power_in"))
      (node (ref "U1") (pin "33") (pinfunction "VDDA_33") (pintype "power_in"))
      (node (ref "U1") (pin "39") (pinfunction "VDD_4_39") (pintype "power_in"))
      (node (ref "U1") (pin "52") (pinfunction "VDD_6_52") (pintype "power_in"))
      (node (ref "U1") (pin "62") (pinfunction "VDD_7_62") (pintype "power_in"))
      (node (ref "U1") (pin "72") (pinfunction "VDD_1_72") (pintype "power_in"))
      (node (ref "U1") (pin "84") (pinfunction "VDD_8_84") (pintype "power_in"))
      (node (ref "U1") (pin "95") (pinfunction "VDD_9_95") (pintype "power_in"))
      (node (ref "U2") (pin "2") (pinfunction "OUT_2") (pintype "passive"))
      (node (ref "U2") (pin "4") (pinfunction "OUT_4") (pintype "passive"))
    )
    (net (code "119") (name "GND") (class "Default")
      (node (ref "BOOT") (pin "1") (pinfunction "1_1") (pintype "passive"))
      (node (ref "BOOT") (pin "2") (pinfunction "2_2") (pintype "passive"))
      (node (ref "C1") (pin "2") (pinfunction "2_2") (pintype "passive"))
      (node (ref "C10") (pin "2") (pinfunction "2_2") (pintype "passive"))
      (node (ref "C11") (pin "2") (pinfunction "2_2") (pintype "passive"))
      (node (ref "C12") (pin "2") (pinfunction "2_2") (pintype "passive"))
      (node (ref "C13") (pin "2") (pinfunction "2_2") (pintype "passive"))
      (node (ref "C14") (pin "2") (pinfunction "2_2") (pintype "passive"))
      (node (ref "C15") (pin "2") (pinfunction "2_2") (pintype "passive"))
      (node (ref "C17") (pin "1") (pinfunction "1_1") (pintype "passive"))
      (node (ref "C18") (pin "1") (pinfunction "1_1") (pintype "passive"))
      (node (ref "C19") (pin "2") (pinfunction "2_2") (pintype "passive"))
      (node (ref "C2") (pin "2") (pinfunction "2_2") (pintype "passive"))
      (node (ref "C3") (pin "1") (pinfunction "1_1") (pintype "passive"))
      (node (ref "C4") (pin "2") (pinfunction "2_2") (pintype "passive"))
      (node (ref "C5") (pin "2") (pinfunction "2_2") (pintype "passive"))
      (node (ref "C6") (pin "2") (pinfunction "2_2") (pintype "passive"))
      (node (ref "C7") (pin "2") (pinfunction "2_2") (pintype "passive"))
      (node (ref "C8") (pin "2") (pinfunction "2_2") (pintype "passive"))
      (node (ref "C9") (pin "2") (pinfunction "2_2") (pintype "passive"))
      (node (ref "JTAG") (pin "10") (pinfunction "10_10") (pintype "passive"))
      (node (ref "JTAG") (pin "12") (pinfunction "12_12") (pintype "passive"))
      (node (ref "JTAG") (pin "14") (pinfunction "14_14") (pintype "passive"))
      (node (ref "JTAG") (pin "16") (pinfunction "16_16") (pintype "passive"))
      (node (ref "JTAG") (pin "18") (pinfunction "18_18") (pintype "passive"))
      (node (ref "JTAG") (pin "20") (pinfunction "20_20") (pintype "passive"))
      (node (ref "JTAG") (pin "4") (pinfunction "4_4") (pintype "passive"))
      (node (ref "JTAG") (pin "6") (pinfunction "6_6") (pintype "passive"))
      (node (ref "JTAG") (pin "8") (pinfunction "8_8") (pintype "passive"))
      (node (ref "KEY") (pin "2") (pinfunction "20_2") (pintype "passive"))
      (node (ref "LED1") (pin "2") (pinfunction "2_2") (pintype "passive"))
      (node (ref "LED2") (pin "2") (pinfunction "2_2") (pintype "passive"))
      (node (ref "LED3") (pin "2") (pinfunction "2_2") (pintype "passive"))
      (node (ref "P1") (pin "2") (pinfunction "2_2") (pintype "passive"))
      (node (ref "P2") (pin "2") (pinfunction "2_2") (pintype "passive"))
      (node (ref "P3") (pin "30") (pinfunction "30_30") (pintype "passive"))
      (node (ref "P4") (pin "29") (pinfunction "29_29") (pintype "passive"))
      (node (ref "R7") (pin "1") (pinfunction "10_1") (pintype "passive"))
      (node (ref "U1") (pin "107") (pinfunction "VSS_2_107") (pintype "power_in"))
      (node (ref "U1") (pin "120") (pinfunction "VSS_10_120") (pintype "power_in"))
      (node (ref "U1") (pin "130") (pinfunction "VSS_11_130") (pintype "power_in"))
      (node (ref "U1") (pin "143") (pinfunction "VSS_3_143") (pintype "power_in"))
      (node (ref "U1") (pin "16") (pinfunction "VSS_5_16") (pintype "power_in"))
      (node (ref "U1") (pin "30") (pinfunction "VSSA_30") (pintype "power_in"))
      (node (ref "U1") (pin "38") (pinfunction "VSS_4_38") (pintype "power_in"))
      (node (ref "U1") (pin "51") (pinfunction "VSS_6_51") (pintype "power_in"))
      (node (ref "U1") (pin "61") (pinfunction "VSS_7_61") (pintype "power_in"))
      (node (ref "U1") (pin "71") (pinfunction "VSS_1_71") (pintype "power_in"))
      (node (ref "U1") (pin "83") (pinfunction "VSS_8_83") (pintype "power_in"))
      (node (ref "U1") (pin "94") (pinfunction "VSS_9_94") (pintype "power_in"))
      (node (ref "U2") (pin "1") (pinfunction "GND_1") (pintype "passive"))
      (node (ref "USB") (pin "5") (pinfunction "GND_5") (pintype "passive"))
    )
    (net (code "120") (name "Net-(R1-11)") (class "Default")
      (node (ref "BOOT") (pin "4") (pinfunction "4_4") (pintype "passive"))
      (node (ref "R1") (pin "2") (pinfunction "11_2") (pintype "passive"))
    )
    (net (code "121") (name "Net-(R2-10)") (class "Default")
      (node (ref "BOOT") (pin "3") (pinfunction "3_3") (pintype "passive"))
      (node (ref "R2") (pin "1") (pinfunction "10_1") (pintype "passive"))
    )
    (net (code "122") (name "Net-(R9-10)") (class "Default")
      (node (ref "LED1") (pin "1") (pinfunction "1_1") (pintype "passive"))
      (node (ref "R9") (pin "1") (pinfunction "10_1") (pintype "passive"))
    )
    (net (code "123") (name "Net-(R10-10)") (class "Default")
      (node (ref "LED2") (pin "1") (pinfunction "1_1") (pintype "passive"))
      (node (ref "R10") (pin "1") (pinfunction "10_1") (pintype "passive"))
    )
    (net (code "124") (name "Net-(R11-10)") (class "Default")
      (node (ref "LED3") (pin "1") (pinfunction "1_1") (pintype "passive"))
      (node (ref "R11") (pin "1") (pinfunction "10_1") (pintype "passive"))
    )
    (net (code "125") (name "Net-(S1-Pad2)") (class "Default")
      (node (ref "S1") (pin "2") (pinfunction "2_2") (pintype "passive"))
      (node (ref "S1") (pin "3") (pinfunction "3_3") (pintype "passive"))
      (node (ref "USB") (pin "1") (pinfunction "VCC_1") (pintype "passive"))
    )
    (net (code "126") (name "Net-(U1-OSC_IN)") (class "Default")
      (node (ref "C1") (pin "1") (pinfunction "1_1") (pintype "passive"))
      (node (ref "U1") (pin "23") (pinfunction "OSC_IN_23") (pintype "input"))
      (node (ref "XATL1") (pin "1") (pinfunction "1_1") (pintype "passive"))
    )
    (net (code "127") (name "Net-(U1-OSC_OUT)") (class "Default")
      (node (ref "C2") (pin "1") (pinfunction "1_1") (pintype "passive"))
      (node (ref "U1") (pin "24") (pinfunction "OSC_OUT_24") (pintype "output"))
      (node (ref "XATL1") (pin "2") (pinfunction "2_2") (pintype "passive"))
    )
    (net (code "128") (name "VCC") (class "Default")
      (node (ref "C17") (pin "2") (pinfunction "2_2") (pintype "passive"))
      (node (ref "P1") (pin "1") (pinfunction "1_1") (pintype "passive"))
      (node (ref "P2") (pin "1") (pinfunction "1_1") (pintype "passive"))
      (node (ref "P3") (pin "29") (pinfunction "29_29") (pintype "passive"))
      (node (ref "P4") (pin "30") (pinfunction "30_30") (pintype "passive"))
      (node (ref "R9") (pin "2") (pinfunction "11_2") (pintype "passive"))
      (node (ref "S1") (pin "1") (pinfunction "1_1") (pintype "passive"))
      (node (ref "U2") (pin "3") (pinfunction "IN_3") (pintype "passive"))
    )
    (net (code "129") (name "unconnected-(JTAG-Pad11)") (class "Default")
      (node (ref "JTAG") (pin "11") (pinfunction "11_11") (pintype "passive+no_connect"))
    )
    (net (code "130") (name "unconnected-(JTAG-Pad17)") (class "Default")
      (node (ref "JTAG") (pin "17") (pinfunction "17_17") (pintype "passive+no_connect"))
    )
    (net (code "131") (name "unconnected-(JTAG-Pad19)") (class "Default")
      (node (ref "JTAG") (pin "19") (pinfunction "19_19") (pintype "passive+no_connect"))
    )
    (net (code "132") (name "unconnected-(S1-Pad4)") (class "Default")
      (node (ref "S1") (pin "4") (pinfunction "4_4") (pintype "passive"))
    )
    (net (code "133") (name "unconnected-(S1-Pad5)") (class "Default")
      (node (ref "S1") (pin "5") (pinfunction "5_5") (pintype "passive"))
    )
    (net (code "134") (name "unconnected-(S1-Pad6)") (class "Default")
      (node (ref "S1") (pin "6") (pinfunction "6_6") (pintype "passive"))
    )
    (net (code "135") (name "unconnected-(U1-NC-Pad106)") (class "Default")
      (node (ref "U1") (pin "106") (pinfunction "NC_106") (pintype "power_in"))
    )
    (net (code "136") (name "unconnected-(USB-VCC-Pad2)") (class "Default")
      (node (ref "USB") (pin "2") (pinfunction "VCC_2") (pintype "passive"))
    )
    (net (code "137") (name "unconnected-(USB-VCC-Pad3)") (class "Default")
      (node (ref "USB") (pin "3") (pinfunction "VCC_3") (pintype "passive"))
    )
    (net (code "138") (name "unconnected-(USB-VCC-Pad4)") (class "Default")
      (node (ref "USB") (pin "4") (pinfunction "VCC_4") (pintype "passive"))
    )
  )
)
